# elatus.net
KiCad netlist of a schematic drawn in EAGLE
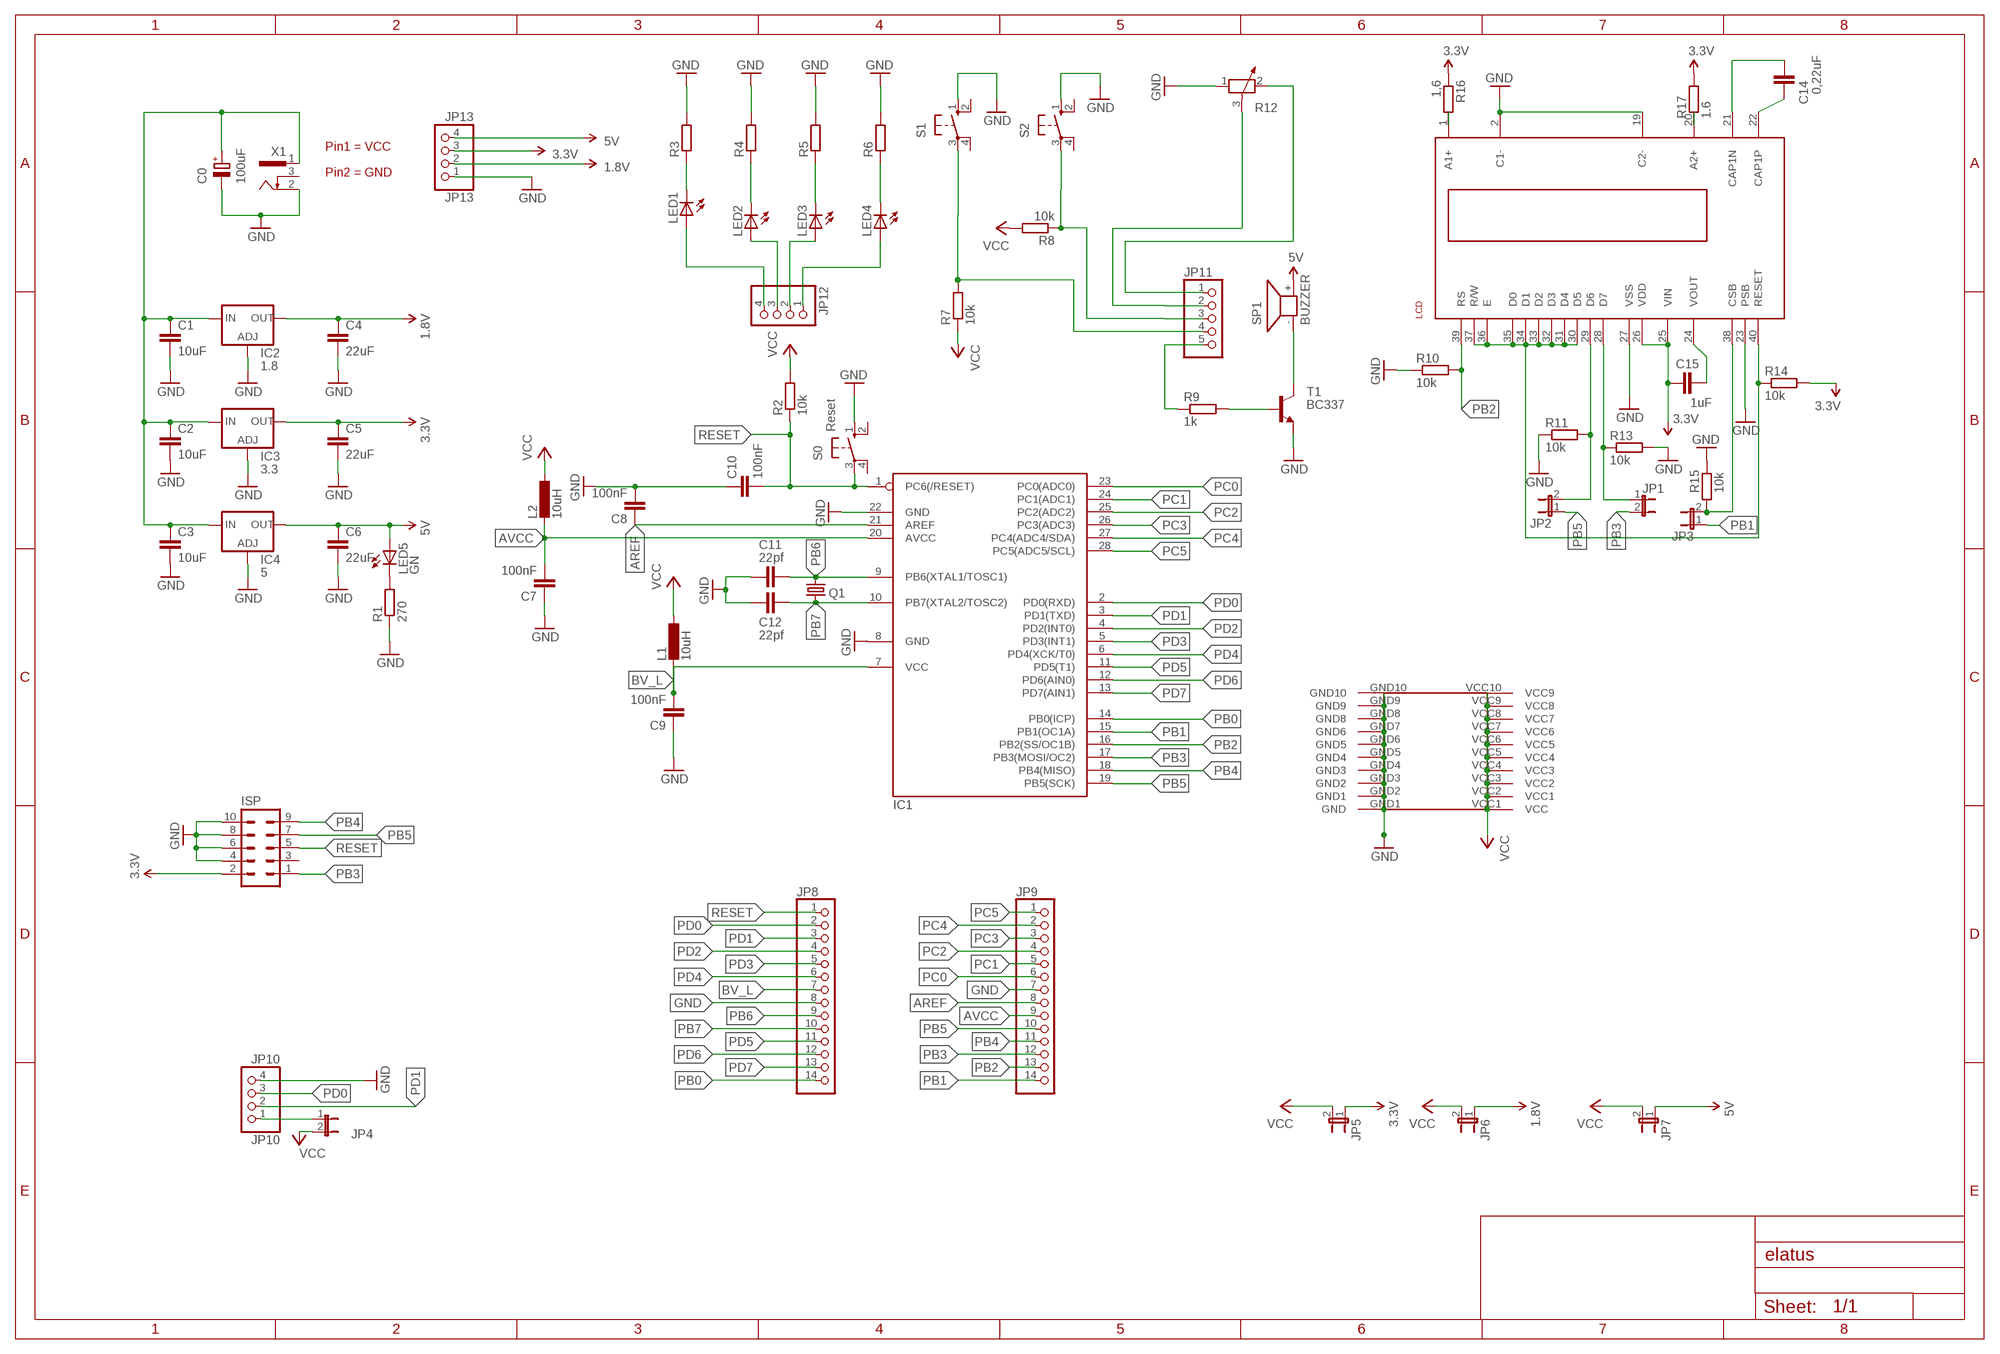
[diagram p0: schematic, sheet 1]

(export (version "E")
  (design (tool "Eeschema 10.0.6"))
  (components
    (comp (ref "C0")
      (value "100uF")
      (footprint "eagle-import:RCL_E2,5-7")
      (libsource (lib "eagle-import") (part "RCL_CPOL-EUE2.5-7"))
    )
    (comp (ref "C1")
      (value "10uF")
      (footprint "eagle-import:RCL_C025-040X050")
      (libsource (lib "eagle-import") (part "RCL_C-EU025-040X050"))
    )
    (comp (ref "C2")
      (value "10uF")
      (footprint "eagle-import:RCL_C025-040X050")
      (libsource (lib "eagle-import") (part "RCL_C-EU025-040X050"))
    )
    (comp (ref "C3")
      (value "10uF")
      (footprint "eagle-import:RCL_C025-040X050")
      (libsource (lib "eagle-import") (part "RCL_C-EU025-040X050"))
    )
    (comp (ref "C4")
      (value "22uF")
      (footprint "eagle-import:RCL_C025-040X050")
      (libsource (lib "eagle-import") (part "RCL_C-EU025-040X050"))
    )
    (comp (ref "C5")
      (value "22uF")
      (footprint "eagle-import:RCL_C025-040X050")
      (libsource (lib "eagle-import") (part "RCL_C-EU025-040X050"))
    )
    (comp (ref "C6")
      (value "22uF")
      (footprint "eagle-import:RCL_C025-040X050")
      (libsource (lib "eagle-import") (part "RCL_C-EU025-040X050"))
    )
    (comp (ref "C7")
      (value "100nF")
      (footprint "eagle-import:RCL_C025-040X050")
      (libsource (lib "eagle-import") (part "RCL_C-EU025-040X050"))
    )
    (comp (ref "C8")
      (value "100nF")
      (footprint "eagle-import:RCL_C025-040X050")
      (libsource (lib "eagle-import") (part "RCL_C-EU025-040X050"))
    )
    (comp (ref "C9")
      (value "100nF")
      (footprint "eagle-import:RCL_C025-040X050")
      (libsource (lib "eagle-import") (part "RCL_C-EU025-040X050"))
    )
    (comp (ref "C10")
      (value "100nF")
      (footprint "eagle-import:RCL_C025-040X050")
      (libsource (lib "eagle-import") (part "RCL_C-EU025-040X050"))
    )
    (comp (ref "C11")
      (value "22pf")
      (footprint "eagle-import:RESISTOR_C050-024X044")
      (libsource (lib "eagle-import") (part "RESISTOR_C-EU050-024X044"))
    )
    (comp (ref "C12")
      (value "22pf")
      (footprint "eagle-import:RESISTOR_C050-024X044")
      (libsource (lib "eagle-import") (part "RESISTOR_C-EU050-024X044"))
    )
    (comp (ref "C14")
      (value "0,22uF")
      (footprint "eagle-import:RCL_C025-040X050")
      (libsource (lib "eagle-import") (part "RCL_C-EU025-040X050"))
    )
    (comp (ref "C15")
      (value "1uF")
      (footprint "eagle-import:RCL_C025-040X050")
      (libsource (lib "eagle-import") (part "RCL_C-EU025-040X050"))
    )
    (comp (ref "IC1")
      (value "MEGA8-P")
      (footprint "eagle-import:DIL28-3")
      (libsource (lib "eagle-import") (part "MEGA8-P"))
    )
    (comp (ref "IC2")
      (value "1.8")
      (footprint "eagle-import:TO220V")
      (libsource (lib "eagle-import") (part "LM1117T-ADJ-V"))
    )
    (comp (ref "IC3")
      (value "3.3")
      (footprint "eagle-import:TO220V")
      (libsource (lib "eagle-import") (part "LM1117T-ADJ-V"))
    )
    (comp (ref "IC4")
      (value "5")
      (footprint "eagle-import:TO220V")
      (libsource (lib "eagle-import") (part "LM1117T-ADJ-V"))
    )
    (comp (ref "ISP")
      (value "CON-HARTING-ML_ML10")
      (footprint "eagle-import:CON-HARTING-ML_ML10")
      (libsource (lib "eagle-import") (part "CON-HARTING-ML_ML10"))
    )
    (comp (ref "JP1")
      (value "JP1E")
      (footprint "eagle-import:JP1")
      (libsource (lib "eagle-import") (part "JP1E"))
    )
    (comp (ref "JP2")
      (value "JP1E")
      (footprint "eagle-import:JP1")
      (libsource (lib "eagle-import") (part "JP1E"))
    )
    (comp (ref "JP3")
      (value "JP1E")
      (footprint "eagle-import:JP1")
      (libsource (lib "eagle-import") (part "JP1E"))
    )
    (comp (ref "JP4")
      (value "JP1E")
      (footprint "eagle-import:JP1")
      (libsource (lib "eagle-import") (part "JP1E"))
    )
    (comp (ref "JP5")
      (value "JP1E")
      (footprint "eagle-import:JP1")
      (libsource (lib "eagle-import") (part "JP1E"))
    )
    (comp (ref "JP6")
      (value "JP1E")
      (footprint "eagle-import:JP1")
      (libsource (lib "eagle-import") (part "JP1E"))
    )
    (comp (ref "JP7")
      (value "JP1E")
      (footprint "eagle-import:JP1")
      (libsource (lib "eagle-import") (part "JP1E"))
    )
    (comp (ref "JP8")
      (value "PINHD-1X14")
      (footprint "eagle-import:1X14")
      (libsource (lib "eagle-import") (part "PINHD-1X14"))
    )
    (comp (ref "JP9")
      (value "PINHD-1X14")
      (footprint "eagle-import:1X14")
      (libsource (lib "eagle-import") (part "PINHD-1X14"))
    )
    (comp (ref "JP10")
      (value "JP10")
      (footprint "eagle-import:1X04")
      (libsource (lib "eagle-import") (part "PINHD-1X4"))
    )
    (comp (ref "JP11")
      (value "PINHD-1X5")
      (footprint "eagle-import:1X05")
      (libsource (lib "eagle-import") (part "PINHD-1X5"))
    )
    (comp (ref "JP12")
      (value "PINHD-1X4")
      (footprint "eagle-import:1X04")
      (libsource (lib "eagle-import") (part "PINHD-1X4"))
    )
    (comp (ref "JP13")
      (value "JP13")
      (footprint "eagle-import:1X04")
      (libsource (lib "eagle-import") (part "PINHD-1X4"))
    )
    (comp (ref "L1")
      (value "10uH")
      (footprint "eagle-import:RCL_2200-12.7")
      (libsource (lib "eagle-import") (part "RCL_L-EU2200-12.7"))
    )
    (comp (ref "L2")
      (value "10uH")
      (footprint "eagle-import:RCL_2200-12.7")
      (libsource (lib "eagle-import") (part "RCL_L-EU2200-12.7"))
    )
    (comp (ref "LCD")
      (value "-OPTO_DOGM")
      (footprint "eagle-import:-OPTO_DOGM")
      (libsource (lib "eagle-import") (part "-OPTO_DOGM"))
    )
    (comp (ref "LED1")
      (value "LED_LED3MM")
      (footprint "eagle-import:LED_LED3MM")
      (libsource (lib "eagle-import") (part "LED_LED3MM"))
    )
    (comp (ref "LED2")
      (value "LED_LED3MM")
      (footprint "eagle-import:LED_LED3MM")
      (libsource (lib "eagle-import") (part "LED_LED3MM"))
    )
    (comp (ref "LED3")
      (value "LED_LED3MM")
      (footprint "eagle-import:LED_LED3MM")
      (libsource (lib "eagle-import") (part "LED_LED3MM"))
    )
    (comp (ref "LED4")
      (value "LED_LED3MM")
      (footprint "eagle-import:LED_LED3MM")
      (libsource (lib "eagle-import") (part "LED_LED3MM"))
    )
    (comp (ref "LED5")
      (value "GN")
      (footprint "eagle-import:LED_LED3MM")
      (libsource (lib "eagle-import") (part "LED_LED3MM"))
    )
    (comp (ref "Q1")
      (value "CRYSTAL_CRYSTALHC49U70")
      (footprint "eagle-import:CRYSTAL_HC49U70")
      (libsource (lib "eagle-import") (part "CRYSTAL_CRYSTALHC49U70"))
    )
    (comp (ref "R1")
      (value "270")
      (footprint "eagle-import:0207_10")
      (libsource (lib "eagle-import") (part "R-EU_0207/10"))
    )
    (comp (ref "R2")
      (value "10k")
      (footprint "eagle-import:0207_10")
      (libsource (lib "eagle-import") (part "R-EU_0207/10"))
    )
    (comp (ref "R3")
      (value "R-EU_0207/10")
      (footprint "eagle-import:0207_10")
      (libsource (lib "eagle-import") (part "R-EU_0207/10"))
    )
    (comp (ref "R4")
      (value "R-EU_0207/10")
      (footprint "eagle-import:0207_10")
      (libsource (lib "eagle-import") (part "R-EU_0207/10"))
    )
    (comp (ref "R5")
      (value "R-EU_0207/10")
      (footprint "eagle-import:0207_10")
      (libsource (lib "eagle-import") (part "R-EU_0207/10"))
    )
    (comp (ref "R6")
      (value "R-EU_0207/10")
      (footprint "eagle-import:0207_10")
      (libsource (lib "eagle-import") (part "R-EU_0207/10"))
    )
    (comp (ref "R7")
      (value "10k")
      (footprint "eagle-import:0207_10")
      (libsource (lib "eagle-import") (part "R-EU_0207/10"))
    )
    (comp (ref "R8")
      (value "10k")
      (footprint "eagle-import:0207_10")
      (libsource (lib "eagle-import") (part "R-EU_0207/10"))
    )
    (comp (ref "R9")
      (value "1k")
      (footprint "eagle-import:0207_10")
      (libsource (lib "eagle-import") (part "R-EU_0207/10"))
    )
    (comp (ref "R10")
      (value "10k")
      (footprint "eagle-import:0207_10")
      (libsource (lib "eagle-import") (part "R-EU_0207/10"))
    )
    (comp (ref "R11")
      (value "10k")
      (footprint "eagle-import:0207_10")
      (libsource (lib "eagle-import") (part "R-EU_0207/10"))
    )
    (comp (ref "R12")
      (value "POTENTIOMETER_PT-10")
      (footprint "eagle-import:PT-10")
      (libsource (lib "eagle-import") (part "POTENTIOMETER_PT-10"))
    )
    (comp (ref "R13")
      (value "10k")
      (footprint "eagle-import:0207_10")
      (libsource (lib "eagle-import") (part "R-EU_0207/10"))
    )
    (comp (ref "R14")
      (value "10k")
      (footprint "eagle-import:0207_10")
      (libsource (lib "eagle-import") (part "R-EU_0207/10"))
    )
    (comp (ref "R15")
      (value "10k")
      (footprint "eagle-import:0207_10")
      (libsource (lib "eagle-import") (part "R-EU_0207/10"))
    )
    (comp (ref "R16")
      (value "1,6")
      (footprint "eagle-import:0207_10")
      (libsource (lib "eagle-import") (part "R-EU_0207/10"))
    )
    (comp (ref "R17")
      (value "1.6")
      (footprint "eagle-import:0207_10")
      (libsource (lib "eagle-import") (part "R-EU_0207/10"))
    )
    (comp (ref "S0")
      (value "Reset")
      (footprint "eagle-import:SWITCH-OMRON_B3F-10XX")
      (libsource (lib "eagle-import") (part "SWITCH-OMRON_10-XX"))
    )
    (comp (ref "S1")
      (value "SWITCH-OMRON_10-XX")
      (footprint "eagle-import:SWITCH-OMRON_B3F-10XX")
      (libsource (lib "eagle-import") (part "SWITCH-OMRON_10-XX"))
    )
    (comp (ref "S2")
      (value "SWITCH-OMRON_10-XX")
      (footprint "eagle-import:SWITCH-OMRON_B3F-10XX")
      (libsource (lib "eagle-import") (part "SWITCH-OMRON_10-XX"))
    )
    (comp (ref "SP1")
      (value "BUZZER")
      (footprint "eagle-import:BUZZER_F_PMX04A")
      (libsource (lib "eagle-import") (part "BUZZER_F/PMX04"))
    )
    (comp (ref "T1")
      (value "BC337")
      (footprint "eagle-import:TO92")
      (libsource (lib "eagle-import") (part "BC337"))
    )
    (comp (ref "U$3")
      (value "JP5")
      (footprint "eagle-import:RASTER_2_54")
      (libsource (lib "eagle-import") (part "RASTER_2_45"))
    )
    (comp (ref "X1")
      (value "CON-CONRAD_733980-62")
      (footprint "eagle-import:CON-CONRAD_733980-62")
      (libsource (lib "eagle-import") (part "CON-CONRAD_73398?0-62"))
    )
  )
  (nets
    (net (code "1") (name "1.8V") (class "Default")
      (node (ref "C4") (pin "1") (pinfunction "1_1") (pintype "passive"))
      (node (ref "IC2") (pin "2") (pinfunction "OUT_2") (pintype "passive"))
      (node (ref "JP13") (pin "2") (pinfunction "2_2") (pintype "passive"))
      (node (ref "JP6") (pin "1") (pinfunction "1_1") (pintype "passive"))
    )
    (net (code "2") (name "3.3V") (class "Default")
      (node (ref "C15") (pin "2") (pinfunction "2_2") (pintype "passive"))
      (node (ref "C5") (pin "1") (pinfunction "1_1") (pintype "passive"))
      (node (ref "IC3") (pin "2") (pinfunction "OUT_2") (pintype "passive"))
      (node (ref "ISP") (pin "2") (pinfunction "2_2") (pintype "passive"))
      (node (ref "JP13") (pin "3") (pinfunction "3_3") (pintype "passive"))
      (node (ref "JP5") (pin "1") (pinfunction "1_1") (pintype "passive"))
      (node (ref "LCD") (pin "25") (pinfunction "VIN_25") (pintype "bidirectional"))
      (node (ref "LCD") (pin "26") (pinfunction "VDD_26") (pintype "bidirectional"))
      (node (ref "R14") (pin "2") (pinfunction "2_2") (pintype "passive"))
      (node (ref "R16") (pin "1") (pinfunction "1_1") (pintype "passive"))
      (node (ref "R17") (pin "2") (pinfunction "2_2") (pintype "passive"))
    )
    (net (code "3") (name "5V") (class "Default")
      (node (ref "C6") (pin "1") (pinfunction "1_1") (pintype "passive"))
      (node (ref "IC4") (pin "2") (pinfunction "OUT_2") (pintype "passive"))
      (node (ref "JP13") (pin "4") (pinfunction "4_4") (pintype "passive"))
      (node (ref "JP7") (pin "1") (pinfunction "1_1") (pintype "passive"))
      (node (ref "LED5") (pin "A") (pinfunction "A_A") (pintype "passive"))
      (node (ref "SP1") (pin "+") (pinfunction "2_+") (pintype "passive"))
    )
    (net (code "4") (name "AREF") (class "Default")
      (node (ref "C8") (pin "1") (pinfunction "1_1") (pintype "passive"))
      (node (ref "IC1") (pin "21") (pinfunction "AREF_21") (pintype "passive"))
      (node (ref "JP9") (pin "8") (pinfunction "8_8") (pintype "passive"))
    )
    (net (code "5") (name "AVCC") (class "Default")
      (node (ref "C7") (pin "2") (pinfunction "2_2") (pintype "passive"))
      (node (ref "IC1") (pin "20") (pinfunction "AVCC_20") (pintype "power_in"))
      (node (ref "JP9") (pin "9") (pinfunction "9_9") (pintype "passive"))
      (node (ref "L2") (pin "2") (pinfunction "2_2") (pintype "passive"))
    )
    (net (code "6") (name "BV_L") (class "Default")
      (node (ref "C9") (pin "2") (pinfunction "2_2") (pintype "passive"))
      (node (ref "IC1") (pin "7") (pinfunction "VCC_7") (pintype "power_in"))
      (node (ref "JP8") (pin "7") (pinfunction "7_7") (pintype "passive"))
      (node (ref "L1") (pin "2") (pinfunction "2_2") (pintype "passive"))
    )
    (net (code "7") (name "GND") (class "Default")
      (node (ref "C0") (pin "-") (pinfunction "-_-") (pintype "passive"))
      (node (ref "C1") (pin "2") (pinfunction "2_2") (pintype "passive"))
      (node (ref "C10") (pin "1") (pinfunction "1_1") (pintype "passive"))
      (node (ref "C11") (pin "1") (pinfunction "1_1") (pintype "passive"))
      (node (ref "C12") (pin "1") (pinfunction "1_1") (pintype "passive"))
      (node (ref "C2") (pin "2") (pinfunction "2_2") (pintype "passive"))
      (node (ref "C3") (pin "2") (pinfunction "2_2") (pintype "passive"))
      (node (ref "C4") (pin "2") (pinfunction "2_2") (pintype "passive"))
      (node (ref "C5") (pin "2") (pinfunction "2_2") (pintype "passive"))
      (node (ref "C6") (pin "2") (pinfunction "2_2") (pintype "passive"))
      (node (ref "C7") (pin "1") (pinfunction "1_1") (pintype "passive"))
      (node (ref "C8") (pin "2") (pinfunction "2_2") (pintype "passive"))
      (node (ref "C9") (pin "1") (pinfunction "1_1") (pintype "passive"))
      (node (ref "IC1") (pin "22") (pinfunction "GND_22") (pintype "power_in"))
      (node (ref "IC1") (pin "8") (pinfunction "GND_8") (pintype "power_in"))
      (node (ref "IC2") (pin "1") (pinfunction "ADJ_1") (pintype "input"))
      (node (ref "IC3") (pin "1") (pinfunction "ADJ_1") (pintype "input"))
      (node (ref "IC4") (pin "1") (pinfunction "ADJ_1") (pintype "input"))
      (node (ref "ISP") (pin "10") (pinfunction "10_10") (pintype "passive"))
      (node (ref "ISP") (pin "4") (pinfunction "4_4") (pintype "passive"))
      (node (ref "ISP") (pin "6") (pinfunction "6_6") (pintype "passive"))
      (node (ref "ISP") (pin "8") (pinfunction "8_8") (pintype "passive"))
      (node (ref "JP10") (pin "4") (pinfunction "4_4") (pintype "passive"))
      (node (ref "JP13") (pin "1") (pinfunction "1_1") (pintype "passive"))
      (node (ref "JP8") (pin "8") (pinfunction "8_8") (pintype "passive"))
      (node (ref "JP9") (pin "7") (pinfunction "7_7") (pintype "passive"))
      (node (ref "LCD") (pin "19") (pinfunction "C2-_19") (pintype "bidirectional"))
      (node (ref "LCD") (pin "2") (pinfunction "C1-_2") (pintype "bidirectional"))
      (node (ref "LCD") (pin "23") (pinfunction "PSB_23") (pintype "bidirectional"))
      (node (ref "LCD") (pin "27") (pinfunction "VSS_27") (pintype "bidirectional"))
      (node (ref "R1") (pin "1") (pinfunction "1_1") (pintype "passive"))
      (node (ref "R10") (pin "1") (pinfunction "1_1") (pintype "passive"))
      (node (ref "R11") (pin "1") (pinfunction "1_1") (pintype "passive"))
      (node (ref "R12") (pin "1") (pinfunction "1_1") (pintype "passive"))
      (node (ref "R13") (pin "2") (pinfunction "2_2") (pintype "passive"))
      (node (ref "R15") (pin "2") (pinfunction "2_2") (pintype "passive"))
      (node (ref "R3") (pin "2") (pinfunction "2_2") (pintype "passive"))
      (node (ref "R4") (pin "2") (pinfunction "2_2") (pintype "passive"))
      (node (ref "R5") (pin "2") (pinfunction "2_2") (pintype "passive"))
      (node (ref "R6") (pin "2") (pinfunction "2_2") (pintype "passive"))
      (node (ref "S0") (pin "1") (pinfunction "S_1") (pintype "passive"))
      (node (ref "S1") (pin "1") (pinfunction "S_1") (pintype "passive"))
      (node (ref "S2") (pin "1") (pinfunction "S_1") (pintype "passive"))
      (node (ref "T1") (pin "1") (pinfunction "E_1") (pintype "passive"))
      (node (ref "U$3") (pin "GND1") (pinfunction "GND_GND1") (pintype "bidirectional"))
      (node (ref "U$3") (pin "GND10") (pinfunction "GND10_GND10") (pintype "bidirectional"))
      (node (ref "U$3") (pin "GND2") (pinfunction "GND1_GND2") (pintype "bidirectional"))
      (node (ref "U$3") (pin "GND3") (pinfunction "GND2_GND3") (pintype "bidirectional"))
      (node (ref "U$3") (pin "GND4") (pinfunction "GND3_GND4") (pintype "bidirectional"))
      (node (ref "U$3") (pin "GND5") (pinfunction "GND4_GND5") (pintype "bidirectional"))
      (node (ref "U$3") (pin "GND6") (pinfunction "GND5_GND6") (pintype "bidirectional"))
      (node (ref "U$3") (pin "GND7") (pinfunction "GND6_GND7") (pintype "bidirectional"))
      (node (ref "U$3") (pin "GND8") (pinfunction "GND8_GND8") (pintype "bidirectional"))
      (node (ref "U$3") (pin "GND9") (pinfunction "GND9_GND9") (pintype "bidirectional"))
      (node (ref "X1") (pin "2") (pinfunction "2_2") (pintype "passive"))
    )
    (net (code "8") (name "Net-(IC2-IN)") (class "Default")
      (node (ref "C0") (pin "+") (pinfunction "+_+") (pintype "passive"))
      (node (ref "C1") (pin "1") (pinfunction "1_1") (pintype "passive"))
      (node (ref "C2") (pin "1") (pinfunction "1_1") (pintype "passive"))
      (node (ref "C3") (pin "1") (pinfunction "1_1") (pintype "passive"))
      (node (ref "IC2") (pin "3") (pinfunction "IN_3") (pintype "input"))
      (node (ref "IC3") (pin "3") (pinfunction "IN_3") (pintype "input"))
      (node (ref "IC4") (pin "3") (pinfunction "IN_3") (pintype "input"))
      (node (ref "X1") (pin "1") (pinfunction "1_1") (pintype "passive"))
    )
    (net (code "9") (name "Net-(JP10-Pad1)") (class "Default")
      (node (ref "JP10") (pin "1") (pinfunction "1_1") (pintype "passive"))
      (node (ref "JP4") (pin "1") (pinfunction "1_1") (pintype "passive"))
    )
    (net (code "10") (name "Net-(JP11-Pad1)") (class "Default")
      (node (ref "JP11") (pin "1") (pinfunction "1_1") (pintype "passive"))
      (node (ref "R12") (pin "2") (pinfunction "2_2") (pintype "passive"))
    )
    (net (code "11") (name "Net-(JP11-Pad2)") (class "Default")
      (node (ref "JP11") (pin "2") (pinfunction "2_2") (pintype "passive"))
      (node (ref "R12") (pin "3") (pinfunction "3_3") (pintype "passive"))
    )
    (net (code "12") (name "Net-(JP11-Pad5)") (class "Default")
      (node (ref "JP11") (pin "5") (pinfunction "5_5") (pintype "passive"))
      (node (ref "R9") (pin "1") (pinfunction "1_1") (pintype "passive"))
    )
    (net (code "13") (name "Net-(JP12-Pad1)") (class "Default")
      (node (ref "JP12") (pin "1") (pinfunction "1_1") (pintype "passive"))
      (node (ref "LED4") (pin "A") (pinfunction "A_A") (pintype "passive"))
    )
    (net (code "14") (name "Net-(JP12-Pad2)") (class "Default")
      (node (ref "JP12") (pin "2") (pinfunction "2_2") (pintype "passive"))
      (node (ref "LED3") (pin "A") (pinfunction "A_A") (pintype "passive"))
    )
    (net (code "15") (name "Net-(JP12-Pad3)") (class "Default")
      (node (ref "JP12") (pin "3") (pinfunction "3_3") (pintype "passive"))
      (node (ref "LED2") (pin "A") (pinfunction "A_A") (pintype "passive"))
    )
    (net (code "16") (name "Net-(JP12-Pad4)") (class "Default")
      (node (ref "JP12") (pin "4") (pinfunction "4_4") (pintype "passive"))
      (node (ref "LED1") (pin "A") (pinfunction "A_A") (pintype "passive"))
    )
    (net (code "17") (name "Net-(LCD-A1+)") (class "Default")
      (node (ref "LCD") (pin "1") (pinfunction "A1+_1") (pintype "bidirectional"))
      (node (ref "R16") (pin "2") (pinfunction "2_2") (pintype "passive"))
    )
    (net (code "18") (name "Net-(LCD-A2+)") (class "Default")
      (node (ref "LCD") (pin "20") (pinfunction "A2+_20") (pintype "bidirectional"))
      (node (ref "R17") (pin "1") (pinfunction "1_1") (pintype "passive"))
    )
    (net (code "19") (name "Net-(LCD-CAP1N)") (class "Default")
      (node (ref "C14") (pin "2") (pinfunction "2_2") (pintype "passive"))
      (node (ref "LCD") (pin "21") (pinfunction "CAP1N_21") (pintype "bidirectional"))
    )
    (net (code "20") (name "Net-(LCD-CAP1P)") (class "Default")
      (node (ref "C14") (pin "1") (pinfunction "1_1") (pintype "passive"))
      (node (ref "LCD") (pin "22") (pinfunction "CAP1P_22") (pintype "bidirectional"))
    )
    (net (code "21") (name "Net-(LCD-CSB)") (class "Default")
      (node (ref "JP3") (pin "2") (pinfunction "2_2") (pintype "passive"))
      (node (ref "LCD") (pin "38") (pinfunction "CSB_38") (pintype "bidirectional"))
      (node (ref "R15") (pin "1") (pinfunction "1_1") (pintype "passive"))
    )
    (net (code "22") (name "Net-(LCD-D0)") (class "Default")
      (node (ref "LCD") (pin "30") (pinfunction "D5_30") (pintype "bidirectional"))
      (node (ref "LCD") (pin "31") (pinfunction "D4_31") (pintype "bidirectional"))
      (node (ref "LCD") (pin "32") (pinfunction "D3_32") (pintype "bidirectional"))
      (node (ref "LCD") (pin "33") (pinfunction "D2_33") (pintype "bidirectional"))
      (node (ref "LCD") (pin "34") (pinfunction "D1_34") (pintype "bidirectional"))
      (node (ref "LCD") (pin "35") (pinfunction "D0_35") (pintype "bidirectional"))
      (node (ref "LCD") (pin "36") (pinfunction "E_36") (pintype "bidirectional"))
      (node (ref "LCD") (pin "37") (pinfunction "R/W_37") (pintype "bidirectional"))
      (node (ref "LCD") (pin "40") (pinfunction "RESET_40") (pintype "bidirectional"))
      (node (ref "R14") (pin "1") (pinfunction "1_1") (pintype "passive"))
    )
    (net (code "23") (name "Net-(LCD-D6)") (class "Default")
      (node (ref "JP2") (pin "2") (pinfunction "2_2") (pintype "passive"))
      (node (ref "LCD") (pin "29") (pinfunction "D6_29") (pintype "bidirectional"))
      (node (ref "R11") (pin "2") (pinfunction "2_2") (pintype "passive"))
    )
    (net (code "24") (name "Net-(LCD-D7)") (class "Default")
      (node (ref "JP1") (pin "1") (pinfunction "1_1") (pintype "passive"))
      (node (ref "LCD") (pin "28") (pinfunction "D7_28") (pintype "bidirectional"))
      (node (ref "R13") (pin "1") (pinfunction "1_1") (pintype "passive"))
    )
    (net (code "25") (name "Net-(LCD-VOUT)") (class "Default")
      (node (ref "C15") (pin "1") (pinfunction "1_1") (pintype "passive"))
      (node (ref "LCD") (pin "24") (pinfunction "VOUT_24") (pintype "bidirectional"))
    )
    (net (code "26") (name "Net-(LED1-C)") (class "Default")
      (node (ref "LED1") (pin "K") (pinfunction "C_K") (pintype "passive"))
      (node (ref "R3") (pin "1") (pinfunction "1_1") (pintype "passive"))
    )
    (net (code "27") (name "Net-(LED2-C)") (class "Default")
      (node (ref "LED2") (pin "K") (pinfunction "C_K") (pintype "passive"))
      (node (ref "R4") (pin "1") (pinfunction "1_1") (pintype "passive"))
    )
    (net (code "28") (name "Net-(LED3-C)") (class "Default")
      (node (ref "LED3") (pin "K") (pinfunction "C_K") (pintype "passive"))
      (node (ref "R5") (pin "1") (pinfunction "1_1") (pintype "passive"))
    )
    (net (code "29") (name "Net-(LED4-C)") (class "Default")
      (node (ref "LED4") (pin "K") (pinfunction "C_K") (pintype "passive"))
      (node (ref "R6") (pin "1") (pinfunction "1_1") (pintype "passive"))
    )
    (net (code "30") (name "Net-(LED5-C)") (class "Default")
      (node (ref "LED5") (pin "K") (pinfunction "C_K") (pintype "passive"))
      (node (ref "R1") (pin "2") (pinfunction "2_2") (pintype "passive"))
    )
    (net (code "31") (name "Net-(S1-P)") (class "Default")
      (node (ref "JP11") (pin "4") (pinfunction "4_4") (pintype "passive"))
      (node (ref "R7") (pin "2") (pinfunction "2_2") (pintype "passive"))
      (node (ref "S1") (pin "3") (pinfunction "P_3") (pintype "passive"))
    )
    (net (code "32") (name "Net-(S2-P)") (class "Default")
      (node (ref "JP11") (pin "3") (pinfunction "3_3") (pintype "passive"))
      (node (ref "R8") (pin "1") (pinfunction "1_1") (pintype "passive"))
      (node (ref "S2") (pin "3") (pinfunction "P_3") (pintype "passive"))
    )
    (net (code "33") (name "Net-(SP1-1)") (class "Default")
      (node (ref "SP1") (pin "-") (pinfunction "1_-") (pintype "passive"))
      (node (ref "T1") (pin "3") (pinfunction "C_3") (pintype "passive"))
    )
    (net (code "34") (name "Net-(T1-B)") (class "Default")
      (node (ref "R9") (pin "2") (pinfunction "2_2") (pintype "passive"))
      (node (ref "T1") (pin "2") (pinfunction "B_2") (pintype "passive"))
    )
    (net (code "35") (name "PB0") (class "Default")
      (node (ref "IC1") (pin "14") (pinfunction "PB0(ICP)_14") (pintype "bidirectional"))
      (node (ref "JP8") (pin "14") (pinfunction "14_14") (pintype "passive"))
    )
    (net (code "36") (name "PB1") (class "Default")
      (node (ref "IC1") (pin "15") (pinfunction "PB1(OC1A)_15") (pintype "bidirectional"))
      (node (ref "JP3") (pin "1") (pinfunction "1_1") (pintype "passive"))
      (node (ref "JP9") (pin "14") (pinfunction "14_14") (pintype "passive"))
    )
    (net (code "37") (name "PB2") (class "Default")
      (node (ref "IC1") (pin "16") (pinfunction "PB2(SS/OC1B)_16") (pintype "bidirectional"))
      (node (ref "JP9") (pin "13") (pinfunction "13_13") (pintype "passive"))
      (node (ref "LCD") (pin "39") (pinfunction "RS_39") (pintype "bidirectional"))
      (node (ref "R10") (pin "2") (pinfunction "2_2") (pintype "passive"))
    )
    (net (code "38") (name "PB3") (class "Default")
      (node (ref "IC1") (pin "17") (pinfunction "PB3(MOSI/OC2)_17") (pintype "bidirectional"))
      (node (ref "ISP") (pin "1") (pinfunction "1_1") (pintype "passive"))
      (node (ref "JP1") (pin "2") (pinfunction "2_2") (pintype "passive"))
      (node (ref "JP9") (pin "12") (pinfunction "12_12") (pintype "passive"))
    )
    (net (code "39") (name "PB4") (class "Default")
      (node (ref "IC1") (pin "18") (pinfunction "PB4(MISO)_18") (pintype "bidirectional"))
      (node (ref "ISP") (pin "9") (pinfunction "9_9") (pintype "passive"))
      (node (ref "JP9") (pin "11") (pinfunction "11_11") (pintype "passive"))
    )
    (net (code "40") (name "PB5") (class "Default")
      (node (ref "IC1") (pin "19") (pinfunction "PB5(SCK)_19") (pintype "bidirectional"))
      (node (ref "ISP") (pin "7") (pinfunction "7_7") (pintype "passive"))
      (node (ref "JP2") (pin "1") (pinfunction "1_1") (pintype "passive"))
      (node (ref "JP9") (pin "10") (pinfunction "10_10") (pintype "passive"))
    )
    (net (code "41") (name "PB6") (class "Default")
      (node (ref "C11") (pin "2") (pinfunction "2_2") (pintype "passive"))
      (node (ref "IC1") (pin "9") (pinfunction "PB6(XTAL1/TOSC1)_9") (pintype "bidirectional"))
      (node (ref "JP8") (pin "9") (pinfunction "9_9") (pintype "passive"))
      (node (ref "Q1") (pin "2") (pinfunction "2_2") (pintype "passive"))
    )
    (net (code "42") (name "PB7") (class "Default")
      (node (ref "C12") (pin "2") (pinfunction "2_2") (pintype "passive"))
      (node (ref "IC1") (pin "10") (pinfunction "PB7(XTAL2/TOSC2)_10") (pintype "bidirectional"))
      (node (ref "JP8") (pin "10") (pinfunction "10_10") (pintype "passive"))
      (node (ref "Q1") (pin "1") (pinfunction "1_1") (pintype "passive"))
    )
    (net (code "43") (name "PC0") (class "Default")
      (node (ref "IC1") (pin "23") (pinfunction "PC0(ADC0)_23") (pintype "bidirectional"))
      (node (ref "JP9") (pin "6") (pinfunction "6_6") (pintype "passive"))
    )
    (net (code "44") (name "PC1") (class "Default")
      (node (ref "IC1") (pin "24") (pinfunction "PC1(ADC1)_24") (pintype "bidirectional"))
      (node (ref "JP9") (pin "5") (pinfunction "5_5") (pintype "passive"))
    )
    (net (code "45") (name "PC2") (class "Default")
      (node (ref "IC1") (pin "25") (pinfunction "PC2(ADC2)_25") (pintype "bidirectional"))
      (node (ref "JP9") (pin "4") (pinfunction "4_4") (pintype "passive"))
    )
    (net (code "46") (name "PC3") (class "Default")
      (node (ref "IC1") (pin "26") (pinfunction "PC3(ADC3)_26") (pintype "bidirectional"))
      (node (ref "JP9") (pin "3") (pinfunction "3_3") (pintype "passive"))
    )
    (net (code "47") (name "PC4") (class "Default")
      (node (ref "IC1") (pin "27") (pinfunction "PC4(ADC4/SDA)_27") (pintype "bidirectional"))
      (node (ref "JP9") (pin "2") (pinfunction "2_2") (pintype "passive"))
    )
    (net (code "48") (name "PC5") (class "Default")
      (node (ref "IC1") (pin "28") (pinfunction "PC5(ADC5/SCL)_28") (pintype "bidirectional"))
      (node (ref "JP9") (pin "1") (pinfunction "1_1") (pintype "passive"))
    )
    (net (code "49") (name "PD0") (class "Default")
      (node (ref "IC1") (pin "2") (pinfunction "PD0(RXD)_2") (pintype "bidirectional"))
      (node (ref "JP10") (pin "3") (pinfunction "3_3") (pintype "passive"))
      (node (ref "JP8") (pin "2") (pinfunction "2_2") (pintype "passive"))
    )
    (net (code "50") (name "PD1") (class "Default")
      (node (ref "IC1") (pin "3") (pinfunction "PD1(TXD)_3") (pintype "bidirectional"))
      (node (ref "JP10") (pin "2") (pinfunction "2_2") (pintype "passive"))
      (node (ref "JP8") (pin "3") (pinfunction "3_3") (pintype "passive"))
    )
    (net (code "51") (name "PD2") (class "Default")
      (node (ref "IC1") (pin "4") (pinfunction "PD2(INT0)_4") (pintype "bidirectional"))
      (node (ref "JP8") (pin "4") (pinfunction "4_4") (pintype "passive"))
    )
    (net (code "52") (name "PD3") (class "Default")
      (node (ref "IC1") (pin "5") (pinfunction "PD3(INT1)_5") (pintype "bidirectional"))
      (node (ref "JP8") (pin "5") (pinfunction "5_5") (pintype "passive"))
    )
    (net (code "53") (name "PD4") (class "Default")
      (node (ref "IC1") (pin "6") (pinfunction "PD4(XCK/T0)_6") (pintype "bidirectional"))
      (node (ref "JP8") (pin "6") (pinfunction "6_6") (pintype "passive"))
    )
    (net (code "54") (name "PD5") (class "Default")
      (node (ref "IC1") (pin "11") (pinfunction "PD5(T1)_11") (pintype "bidirectional"))
      (node (ref "JP8") (pin "11") (pinfunction "11_11") (pintype "passive"))
    )
    (net (code "55") (name "PD6") (class "Default")
      (node (ref "IC1") (pin "12") (pinfunction "PD6(AIN0)_12") (pintype "bidirectional"))
      (node (ref "JP8") (pin "12") (pinfunction "12_12") (pintype "passive"))
    )
    (net (code "56") (name "PD7") (class "Default")
      (node (ref "IC1") (pin "13") (pinfunction "PD7(AIN1)_13") (pintype "bidirectional"))
      (node (ref "JP8") (pin "13") (pinfunction "13_13") (pintype "passive"))
    )
    (net (code "57") (name "RESET") (class "Default")
      (node (ref "C10") (pin "2") (pinfunction "2_2") (pintype "passive"))
      (node (ref "IC1") (pin "1") (pinfunction "PC6(/RESET)_1") (pintype "bidirectional"))
      (node (ref "ISP") (pin "5") (pinfunction "5_5") (pintype "passive"))
      (node (ref "JP8") (pin "1") (pinfunction "1_1") (pintype "passive"))
      (node (ref "R2") (pin "1") (pinfunction "1_1") (pintype "passive"))
      (node (ref "S0") (pin "3") (pinfunction "P_3") (pintype "passive"))
    )
    (net (code "58") (name "VCC") (class "Default")
      (node (ref "JP4") (pin "2") (pinfunction "2_2") (pintype "passive"))
      (node (ref "JP5") (pin "2") (pinfunction "2_2") (pintype "passive"))
      (node (ref "JP6") (pin "2") (pinfunction "2_2") (pintype "passive"))
      (node (ref "JP7") (pin "2") (pinfunction "2_2") (pintype "passive"))
      (node (ref "L1") (pin "1") (pinfunction "1_1") (pintype "passive"))
      (node (ref "L2") (pin "1") (pinfunction "1_1") (pintype "passive"))
      (node (ref "R2") (pin "2") (pinfunction "2_2") (pintype "passive"))
      (node (ref "R7") (pin "1") (pinfunction "1_1") (pintype "passive"))
      (node (ref "R8") (pin "2") (pinfunction "2_2") (pintype "passive"))
      (node (ref "U$3") (pin "VCC1") (pinfunction "VCC_VCC1") (pintype "bidirectional"))
      (node (ref "U$3") (pin "VCC10") (pinfunction "VCC9_VCC10") (pintype "bidirectional"))
      (node (ref "U$3") (pin "VCC2") (pinfunction "VCC1_VCC2") (pintype "bidirectional"))
      (node (ref "U$3") (pin "VCC3") (pinfunction "VCC2_VCC3") (pintype "bidirectional"))
      (node (ref "U$3") (pin "VCC4") (pinfunction "VCC3_VCC4") (pintype "bidirectional"))
      (node (ref "U$3") (pin "VCC5") (pinfunction "VCC4_VCC5") (pintype "bidirectional"))
      (node (ref "U$3") (pin "VCC6") (pinfunction "VCC5_VCC6") (pintype "bidirectional"))
      (node (ref "U$3") (pin "VCC7") (pinfunction "VCC6_VCC7") (pintype "bidirectional"))
      (node (ref "U$3") (pin "VCC8") (pinfunction "VCC7_VCC8") (pintype "bidirectional"))
      (node (ref "U$3") (pin "VCC9") (pinfunction "VCC8_VCC9") (pintype "bidirectional"))
    )
    (net (code "59") (name "unconnected-(ISP-Pad3)") (class "Default")
      (node (ref "ISP") (pin "3") (pinfunction "3_3") (pintype "passive"))
    )
    (net (code "60") (name "unconnected-(S0-P1-Pad4)") (class "Default")
      (node (ref "S0") (pin "4") (pinfunction "P1_4") (pintype "passive"))
    )
    (net (code "61") (name "unconnected-(S0-S1-Pad2)") (class "Default")
      (node (ref "S0") (pin "2") (pinfunction "S1_2") (pintype "passive"))
    )
    (net (code "62") (name "unconnected-(S1-P1-Pad4)") (class "Default")
      (node (ref "S1") (pin "4") (pinfunction "P1_4") (pintype "passive"))
    )
    (net (code "63") (name "unconnected-(S1-S1-Pad2)") (class "Default")
      (node (ref "S1") (pin "2") (pinfunction "S1_2") (pintype "passive"))
    )
    (net (code "64") (name "unconnected-(S2-P1-Pad4)") (class "Default")
      (node (ref "S2") (pin "4") (pinfunction "P1_4") (pintype "passive"))
    )
    (net (code "65") (name "unconnected-(S2-S1-Pad2)") (class "Default")
      (node (ref "S2") (pin "2") (pinfunction "S1_2") (pintype "passive"))
    )
    (net (code "66") (name "unconnected-(X1-Pad3)") (class "Default")
      (node (ref "X1") (pin "3") (pinfunction "3_3") (pintype "passive"))
    )
  )
)
